# OpenBLC_LTC4412.net
KiCad netlist of a schematic drawn in Altium Designer
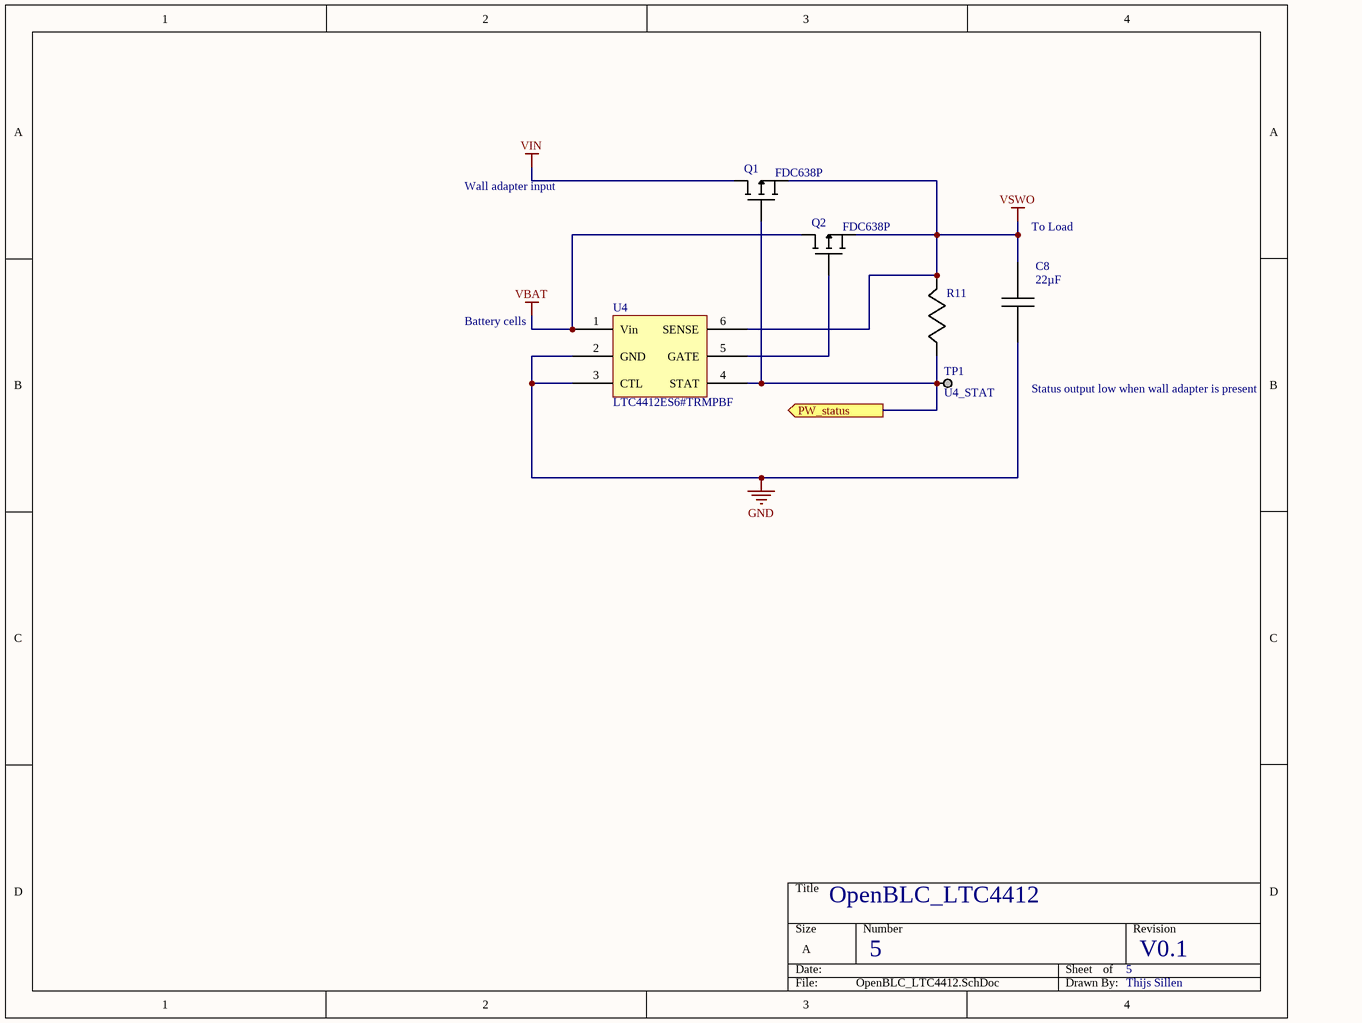
[diagram p0: OpenBLC_LTC4412.SchDoc]

(export (version "E")
  (design (tool "Eeschema 10.0.6"))
  (components
    (comp (ref "C8")
      (value "C2012X5R0J226M125AC")
      (footprint "0805_CAP")
      (description "CAP CER 22UF 6.3V 20% X5R 0805")
      (fields
        (field (name "MANUFACTURER") "TDK Corporation")
        (field (name "TOLERANCE") "±20%")
        (field (name "CAPACITANCE") "22µF")
      )
      (libsource (lib "Schlib1") (part "C2012X5R0J226M125AC"))
    )
    (comp (ref "Q1")
      (value "FDC638P")
      (footprint "FDC638P")
      (description "MOSFET SSOT-6 P-CH -20V")
      (fields
        (field (name "MANUFACTURER") "Fairchild Semiconductor")
        (field (name "MANUFACTURER PART NUMBER") "FDC638P")
      )
      (libsource (lib "Schlib1") (part "FDC638P"))
    )
    (comp (ref "Q2")
      (value "FDC638P")
      (footprint "FDC638P")
      (description "MOSFET SSOT-6 P-CH -20V")
      (fields
        (field (name "MANUFACTURER") "Fairchild Semiconductor")
        (field (name "MANUFACTURER PART NUMBER") "FDC638P")
      )
      (libsource (lib "Schlib1") (part "FDC638P"))
    )
    (comp (ref "R11") (value "0805_RES") (footprint "0805_RES") (libsource (lib "Schlib1") (part "0805_RES")))
    (comp (ref "TP1")
      (value "U4_STAT")
      (footprint "Via_TP")
      (description "TESTPOINT SCOPE GRABBER")
      (fields
        (field (name "MANUFACTURER PART NUMBER") "5010")
        (field (name "MANUFACTURER") "Keystone Electronics")
      )
      (libsource (lib "vh_altium_library") (part "TESTPOINT"))
    )
    (comp (ref "U4")
      (value "LTC4412ES6#TRMPBF")
      (footprint "SOT95P280X110-6N")
      (description "IC OR CTRLR SRC SELECT TSOT23-6")
      (fields
        (field (name "MANUFACTURER") "Linear Technology")
        (field (name "MANUFACTURER PART NUMBER") "LTC4412ES6#TRMPBF")
      )
      (libsource (lib "Schlib1") (part "LTC4412ES6#TRMPBF"))
    )
  )
  (nets
    (net (code "1") (name "/PW_status") (class "Default")
      (node (ref "Q1") (pin "2") (pinfunction "G_2") (pintype "passive"))
      (node (ref "R11") (pin "2") (pinfunction "2_2") (pintype "passive"))
      (node (ref "TP1") (pin "1") (pinfunction "1_1") (pintype "passive"))
      (node (ref "U4") (pin "4") (pinfunction "STAT_4") (pintype "passive"))
    )
    (net (code "2") (name "GND") (class "Default")
      (node (ref "C8") (pin "2") (pinfunction "2_2") (pintype "passive"))
      (node (ref "U4") (pin "2") (pinfunction "GND_2") (pintype "passive"))
      (node (ref "U4") (pin "3") (pinfunction "CTL_3") (pintype "passive"))
    )
    (net (code "3") (name "Net-(Q2-G)") (class "Default")
      (node (ref "Q2") (pin "2") (pinfunction "G_2") (pintype "passive"))
      (node (ref "U4") (pin "5") (pinfunction "GATE_5") (pintype "passive"))
    )
    (net (code "4") (name "VBAT") (class "Default")
      (node (ref "Q2") (pin "1") (pinfunction "D_1") (pintype "passive"))
      (node (ref "U4") (pin "1") (pinfunction "Vin_1") (pintype "passive"))
    )
    (net (code "5") (name "VIN") (class "Default")
      (node (ref "Q1") (pin "1") (pinfunction "D_1") (pintype "passive"))
    )
    (net (code "6") (name "VSWO") (class "Default")
      (node (ref "C8") (pin "1") (pinfunction "1_1") (pintype "passive"))
      (node (ref "Q1") (pin "3") (pinfunction "S_3") (pintype "passive"))
      (node (ref "Q2") (pin "3") (pinfunction "S_3") (pintype "passive"))
      (node (ref "R11") (pin "1") (pinfunction "1_1") (pintype "passive"))
      (node (ref "U4") (pin "6") (pinfunction "SENSE_6") (pintype "passive"))
    )
  )
)
